# a.net
KiCad netlist of a schematic drawn in EAGLE
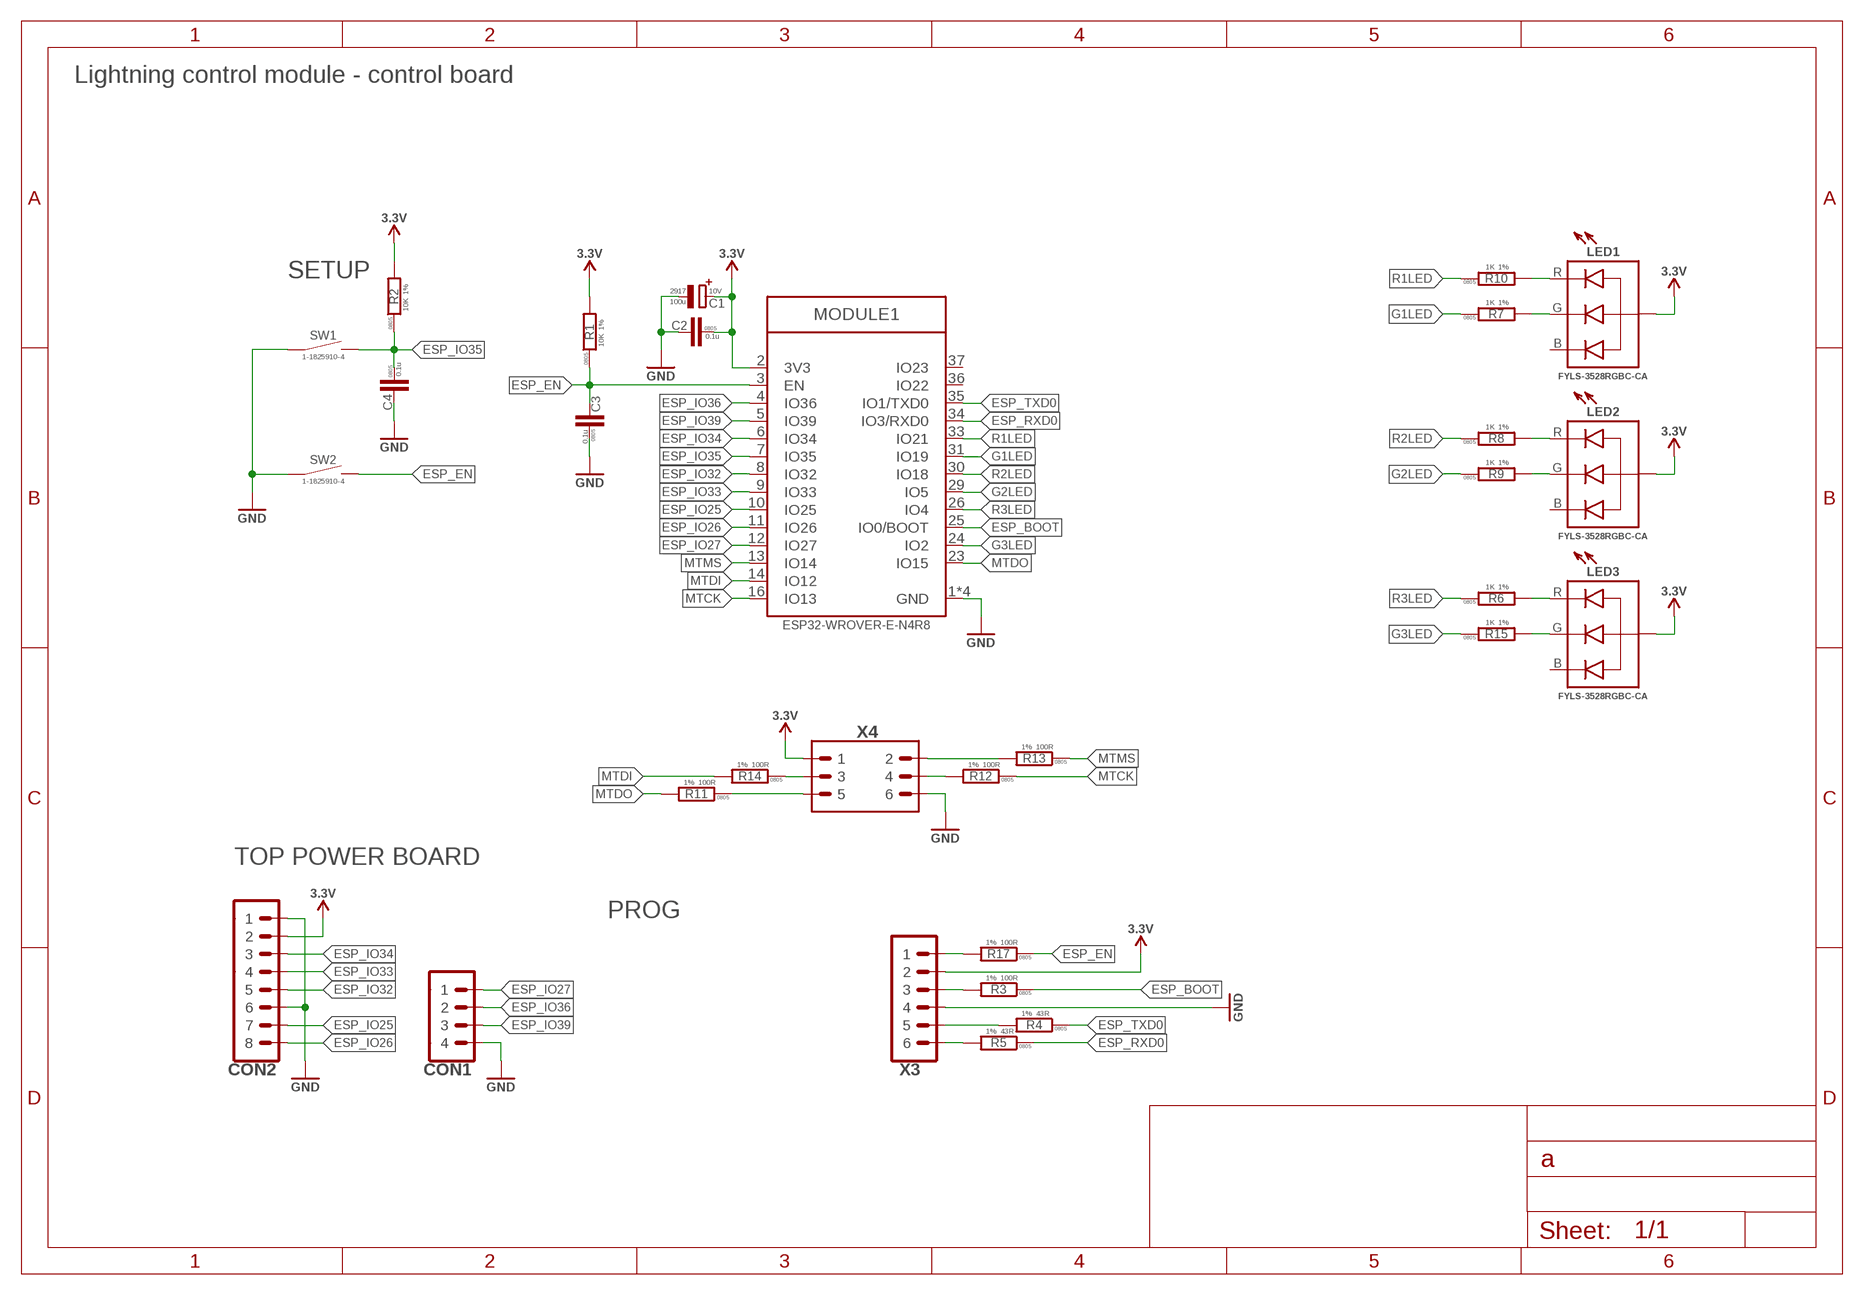
[diagram p0: schematic, sheet 1]

(export (version "E")
  (design (tool "Eeschema 10.0.6"))
  (components
    (comp (ref "C1")
      (value "100u")
      (footprint "eagle-import:C2917")
      (fields (field (name "PACKAGE") "2917") (field (name "VOLTAGE") "10V"))
      (libsource (lib "eagle-import") (part "CPOL-2917"))
    )
    (comp (ref "C2")
      (value "0.1u")
      (footprint "eagle-import:C0805")
      (fields (field (name "PACKAGE") "0805"))
      (libsource (lib "eagle-import") (part "C-0805"))
    )
    (comp (ref "C3")
      (value "0.1u")
      (footprint "eagle-import:C0805")
      (fields (field (name "PACKAGE") "0805"))
      (libsource (lib "eagle-import") (part "C-0805"))
    )
    (comp (ref "C4")
      (value "0.1u")
      (footprint "eagle-import:C0805")
      (fields (field (name "PACKAGE") "0805"))
      (libsource (lib "eagle-import") (part "C-0805"))
    )
    (comp (ref "CON1")
      (value "PINHEAD_1X04-2.54")
      (footprint "eagle-import:1X04-PTH-2.54")
      (libsource (lib "eagle-import") (part "PINHEAD_1X04-2.54"))
    )
    (comp (ref "CON2")
      (value "PINHEAD_1X08-2.54")
      (footprint "eagle-import:1X08-PTH-2.54")
      (libsource (lib "eagle-import") (part "PINHEAD_1X08-2.54"))
    )
    (comp (ref "LED1")
      (value "LED_RGB-3528")
      (footprint "eagle-import:LED3528")
      (fields (field (name "MANF#") "FYLS-3528RGBC-CA") (field (name "MANF") "Foryard"))
      (libsource (lib "eagle-import") (part "LED_RGB-3528"))
    )
    (comp (ref "LED2")
      (value "LED_RGB-3528")
      (footprint "eagle-import:LED3528")
      (fields (field (name "MANF#") "FYLS-3528RGBC-CA") (field (name "MANF") "Foryard"))
      (libsource (lib "eagle-import") (part "LED_RGB-3528"))
    )
    (comp (ref "LED3")
      (value "LED_RGB-3528")
      (footprint "eagle-import:LED3528")
      (fields (field (name "MANF#") "FYLS-3528RGBC-CA") (field (name "MANF") "Foryard"))
      (libsource (lib "eagle-import") (part "LED_RGB-3528"))
    )
    (comp (ref "MODULE1")
      (value "ESP32-WROVER-(I)E")
      (footprint "eagle-import:ESP32-WROVER-E")
      (fields (field (name "MANF#") "ESP32-WROVER-E-N4R8") (field (name "MANF") "Espressif Systems"))
      (libsource (lib "eagle-import") (part "ESP32-WROVER-(I)E"))
    )
    (comp (ref "R1")
      (value "10K")
      (footprint "eagle-import:R0805")
      (fields (field (name "PACKAGE") "0805") (field (name "TOLERANCE") "1%"))
      (libsource (lib "eagle-import") (part "R-0805-1%"))
    )
    (comp (ref "R2")
      (value "10K")
      (footprint "eagle-import:R0805")
      (fields (field (name "PACKAGE") "0805") (field (name "TOLERANCE") "1%"))
      (libsource (lib "eagle-import") (part "R-0805-1%"))
    )
    (comp (ref "R3")
      (value "100R")
      (footprint "eagle-import:R0805")
      (fields (field (name "PACKAGE") "0805") (field (name "TOLERANCE") "1%"))
      (libsource (lib "eagle-import") (part "R-0805-1%"))
    )
    (comp (ref "R4")
      (value "43R")
      (footprint "eagle-import:R0805")
      (fields (field (name "PACKAGE") "0805") (field (name "TOLERANCE") "1%"))
      (libsource (lib "eagle-import") (part "R-0805-1%"))
    )
    (comp (ref "R5")
      (value "43R")
      (footprint "eagle-import:R0805")
      (fields (field (name "PACKAGE") "0805") (field (name "TOLERANCE") "1%"))
      (libsource (lib "eagle-import") (part "R-0805-1%"))
    )
    (comp (ref "R6")
      (value "1K")
      (footprint "eagle-import:R0805")
      (fields (field (name "PACKAGE") "0805") (field (name "TOLERANCE") "1%"))
      (libsource (lib "eagle-import") (part "R-0805-1%"))
    )
    (comp (ref "R7")
      (value "1K")
      (footprint "eagle-import:R0805")
      (fields (field (name "PACKAGE") "0805") (field (name "TOLERANCE") "1%"))
      (libsource (lib "eagle-import") (part "R-0805-1%"))
    )
    (comp (ref "R8")
      (value "1K")
      (footprint "eagle-import:R0805")
      (fields (field (name "PACKAGE") "0805") (field (name "TOLERANCE") "1%"))
      (libsource (lib "eagle-import") (part "R-0805-1%"))
    )
    (comp (ref "R9")
      (value "1K")
      (footprint "eagle-import:R0805")
      (fields (field (name "PACKAGE") "0805") (field (name "TOLERANCE") "1%"))
      (libsource (lib "eagle-import") (part "R-0805-1%"))
    )
    (comp (ref "R10")
      (value "1K")
      (footprint "eagle-import:R0805")
      (fields (field (name "PACKAGE") "0805") (field (name "TOLERANCE") "1%"))
      (libsource (lib "eagle-import") (part "R-0805-1%"))
    )
    (comp (ref "R11")
      (value "100R")
      (footprint "eagle-import:R0805")
      (fields (field (name "PACKAGE") "0805") (field (name "TOLERANCE") "1%"))
      (libsource (lib "eagle-import") (part "R-0805-1%"))
    )
    (comp (ref "R12")
      (value "100R")
      (footprint "eagle-import:R0805")
      (fields (field (name "PACKAGE") "0805") (field (name "TOLERANCE") "1%"))
      (libsource (lib "eagle-import") (part "R-0805-1%"))
    )
    (comp (ref "R13")
      (value "100R")
      (footprint "eagle-import:R0805")
      (fields (field (name "PACKAGE") "0805") (field (name "TOLERANCE") "1%"))
      (libsource (lib "eagle-import") (part "R-0805-1%"))
    )
    (comp (ref "R14")
      (value "100R")
      (footprint "eagle-import:R0805")
      (fields (field (name "PACKAGE") "0805") (field (name "TOLERANCE") "1%"))
      (libsource (lib "eagle-import") (part "R-0805-1%"))
    )
    (comp (ref "R15")
      (value "1K")
      (footprint "eagle-import:R0805")
      (fields (field (name "PACKAGE") "0805") (field (name "TOLERANCE") "1%"))
      (libsource (lib "eagle-import") (part "R-0805-1%"))
    )
    (comp (ref "R17")
      (value "100R")
      (footprint "eagle-import:R0805")
      (fields (field (name "PACKAGE") "0805") (field (name "TOLERANCE") "1%"))
      (libsource (lib "eagle-import") (part "R-0805-1%"))
    )
    (comp (ref "SW1")
      (value "TACT_SWITCH-1-1825910-4")
      (footprint "eagle-import:1-1825910-4")
      (fields (field (name "MANF") "TE Connectivity"))
      (libsource (lib "eagle-import") (part "TACT_SWITCH-1-1825910-4"))
    )
    (comp (ref "SW2")
      (value "TACT_SWITCH-1-1825910-4")
      (footprint "eagle-import:1-1825910-4")
      (fields (field (name "MANF") "TE Connectivity"))
      (libsource (lib "eagle-import") (part "TACT_SWITCH-1-1825910-4"))
    )
    (comp (ref "X3")
      (value "PINHEAD_1X06-2-MALE")
      (footprint "eagle-import:1X06-PTH-2")
      (libsource (lib "eagle-import") (part "PINHEAD_1X06-2-MALE"))
    )
    (comp (ref "X4")
      (value "PINHEAD_2X03-PTH-2.54")
      (footprint "eagle-import:2X03-PTH-2.54")
      (libsource (lib "eagle-import") (part "PINHEAD_2X03-PTH-2.54"))
    )
  )
  (nets
    (net (code "1") (name "3.3V") (class "Default")
      (node (ref "C1") (pin "+") (pinfunction "+_+") (pintype "passive"))
      (node (ref "C2") (pin "1") (pinfunction "1_1") (pintype "passive"))
      (node (ref "CON2") (pin "2") (pinfunction "2_2") (pintype "passive"))
      (node (ref "LED1") (pin "2") (pinfunction "A_2") (pintype "bidirectional"))
      (node (ref "LED2") (pin "2") (pinfunction "A_2") (pintype "bidirectional"))
      (node (ref "LED3") (pin "2") (pinfunction "A_2") (pintype "bidirectional"))
      (node (ref "MODULE1") (pin "2") (pinfunction "3V3_2") (pintype "passive"))
      (node (ref "R1") (pin "2") (pinfunction "2_2") (pintype "passive"))
      (node (ref "R2") (pin "2") (pinfunction "2_2") (pintype "passive"))
      (node (ref "X3") (pin "2") (pinfunction "2_2") (pintype "passive"))
      (node (ref "X4") (pin "1") (pinfunction "1_1") (pintype "passive"))
    )
    (net (code "2") (name "ESP_BOOT") (class "Default")
      (node (ref "MODULE1") (pin "25") (pinfunction "IO0/BOOT_25") (pintype "tri_state"))
      (node (ref "R3") (pin "1") (pinfunction "1_1") (pintype "passive"))
    )
    (net (code "3") (name "ESP_EN") (class "Default")
      (node (ref "C3") (pin "2") (pinfunction "2_2") (pintype "passive"))
      (node (ref "MODULE1") (pin "3") (pinfunction "EN_3") (pintype "tri_state"))
      (node (ref "R1") (pin "1") (pinfunction "1_1") (pintype "passive"))
      (node (ref "R17") (pin "1") (pinfunction "1_1") (pintype "passive"))
      (node (ref "SW2") (pin "3") (pinfunction "2_3") (pintype "bidirectional"))
      (node (ref "SW2") (pin "4") (pinfunction "2_4") (pintype "bidirectional"))
    )
    (net (code "4") (name "ESP_IO25") (class "Default")
      (node (ref "CON2") (pin "7") (pinfunction "7_7") (pintype "passive"))
      (node (ref "MODULE1") (pin "10") (pinfunction "IO25_10") (pintype "tri_state"))
    )
    (net (code "5") (name "ESP_IO26") (class "Default")
      (node (ref "CON2") (pin "8") (pinfunction "8_8") (pintype "passive"))
      (node (ref "MODULE1") (pin "11") (pinfunction "IO26_11") (pintype "tri_state"))
    )
    (net (code "6") (name "ESP_IO27") (class "Default")
      (node (ref "CON1") (pin "1") (pinfunction "1_1") (pintype "passive"))
      (node (ref "MODULE1") (pin "12") (pinfunction "IO27_12") (pintype "tri_state"))
    )
    (net (code "7") (name "ESP_IO32") (class "Default")
      (node (ref "CON2") (pin "5") (pinfunction "5_5") (pintype "passive"))
      (node (ref "MODULE1") (pin "8") (pinfunction "IO32_8") (pintype "tri_state"))
    )
    (net (code "8") (name "ESP_IO33") (class "Default")
      (node (ref "CON2") (pin "4") (pinfunction "4_4") (pintype "passive"))
      (node (ref "MODULE1") (pin "9") (pinfunction "IO33_9") (pintype "tri_state"))
    )
    (net (code "9") (name "ESP_IO34") (class "Default")
      (node (ref "CON2") (pin "3") (pinfunction "3_3") (pintype "passive"))
      (node (ref "MODULE1") (pin "6") (pinfunction "IO34_6") (pintype "tri_state"))
    )
    (net (code "10") (name "ESP_IO35") (class "Default")
      (node (ref "C4") (pin "1") (pinfunction "1_1") (pintype "passive"))
      (node (ref "MODULE1") (pin "7") (pinfunction "IO35_7") (pintype "tri_state"))
      (node (ref "R2") (pin "1") (pinfunction "1_1") (pintype "passive"))
      (node (ref "SW1") (pin "3") (pinfunction "2_3") (pintype "bidirectional"))
      (node (ref "SW1") (pin "4") (pinfunction "2_4") (pintype "bidirectional"))
    )
    (net (code "11") (name "ESP_IO36") (class "Default")
      (node (ref "CON1") (pin "2") (pinfunction "2_2") (pintype "passive"))
      (node (ref "MODULE1") (pin "4") (pinfunction "IO36_4") (pintype "tri_state"))
    )
    (net (code "12") (name "ESP_IO39") (class "Default")
      (node (ref "CON1") (pin "3") (pinfunction "3_3") (pintype "passive"))
      (node (ref "MODULE1") (pin "5") (pinfunction "IO39_5") (pintype "tri_state"))
    )
    (net (code "13") (name "ESP_RXD0") (class "Default")
      (node (ref "MODULE1") (pin "34") (pinfunction "IO3/RXD0_34") (pintype "tri_state"))
      (node (ref "R5") (pin "1") (pinfunction "1_1") (pintype "passive"))
    )
    (net (code "14") (name "ESP_TXD0") (class "Default")
      (node (ref "MODULE1") (pin "35") (pinfunction "IO1/TXD0_35") (pintype "tri_state"))
      (node (ref "R4") (pin "1") (pinfunction "1_1") (pintype "passive"))
    )
    (net (code "15") (name "G1LED") (class "Default")
      (node (ref "MODULE1") (pin "31") (pinfunction "IO19_31") (pintype "tri_state"))
      (node (ref "R7") (pin "1") (pinfunction "1_1") (pintype "passive"))
    )
    (net (code "16") (name "G2LED") (class "Default")
      (node (ref "MODULE1") (pin "29") (pinfunction "IO5_29") (pintype "tri_state"))
      (node (ref "R9") (pin "1") (pinfunction "1_1") (pintype "passive"))
    )
    (net (code "17") (name "G3LED") (class "Default")
      (node (ref "MODULE1") (pin "24") (pinfunction "IO2_24") (pintype "tri_state"))
      (node (ref "R15") (pin "1") (pinfunction "1_1") (pintype "passive"))
    )
    (net (code "18") (name "GND") (class "Default")
      (node (ref "C1") (pin "-") (pinfunction "-_-") (pintype "passive"))
      (node (ref "C2") (pin "2") (pinfunction "2_2") (pintype "passive"))
      (node (ref "C3") (pin "1") (pinfunction "1_1") (pintype "passive"))
      (node (ref "C4") (pin "2") (pinfunction "2_2") (pintype "passive"))
      (node (ref "CON1") (pin "4") (pinfunction "4_4") (pintype "passive"))
      (node (ref "CON2") (pin "1") (pinfunction "1_1") (pintype "passive"))
      (node (ref "CON2") (pin "6") (pinfunction "6_6") (pintype "passive"))
      (node (ref "MODULE1") (pin "1") (pinfunction "GND_1") (pintype "tri_state"))
      (node (ref "MODULE1") (pin "15") (pinfunction "GND_15") (pintype "tri_state"))
      (node (ref "MODULE1") (pin "38") (pinfunction "GND_38") (pintype "tri_state"))
      (node (ref "MODULE1") (pin "39") (pinfunction "GND_39") (pintype "tri_state"))
      (node (ref "SW1") (pin "1") (pinfunction "1_1") (pintype "bidirectional"))
      (node (ref "SW1") (pin "2") (pinfunction "1_2") (pintype "bidirectional"))
      (node (ref "SW2") (pin "1") (pinfunction "1_1") (pintype "bidirectional"))
      (node (ref "SW2") (pin "2") (pinfunction "1_2") (pintype "bidirectional"))
      (node (ref "X3") (pin "4") (pinfunction "4_4") (pintype "passive"))
      (node (ref "X4") (pin "6") (pinfunction "6_6") (pintype "passive"))
    )
    (net (code "19") (name "MTCK") (class "Default")
      (node (ref "MODULE1") (pin "16") (pinfunction "IO13_16") (pintype "tri_state"))
      (node (ref "R12") (pin "1") (pinfunction "1_1") (pintype "passive"))
    )
    (net (code "20") (name "MTDI") (class "Default")
      (node (ref "MODULE1") (pin "14") (pinfunction "IO12_14") (pintype "tri_state"))
      (node (ref "R14") (pin "2") (pinfunction "2_2") (pintype "passive"))
    )
    (net (code "21") (name "MTDO") (class "Default")
      (node (ref "MODULE1") (pin "23") (pinfunction "IO15_23") (pintype "tri_state"))
      (node (ref "R11") (pin "2") (pinfunction "2_2") (pintype "passive"))
    )
    (net (code "22") (name "MTMS") (class "Default")
      (node (ref "MODULE1") (pin "13") (pinfunction "IO14_13") (pintype "tri_state"))
      (node (ref "R13") (pin "1") (pinfunction "1_1") (pintype "passive"))
    )
    (net (code "23") (name "Net-(LED1-G)") (class "Default")
      (node (ref "LED1") (pin "4") (pinfunction "G_4") (pintype "bidirectional"))
      (node (ref "R7") (pin "2") (pinfunction "2_2") (pintype "passive"))
    )
    (net (code "24") (name "Net-(LED1-R)") (class "Default")
      (node (ref "LED1") (pin "1") (pinfunction "R_1") (pintype "bidirectional"))
      (node (ref "R10") (pin "2") (pinfunction "2_2") (pintype "passive"))
    )
    (net (code "25") (name "Net-(LED2-G)") (class "Default")
      (node (ref "LED2") (pin "4") (pinfunction "G_4") (pintype "bidirectional"))
      (node (ref "R9") (pin "2") (pinfunction "2_2") (pintype "passive"))
    )
    (net (code "26") (name "Net-(LED2-R)") (class "Default")
      (node (ref "LED2") (pin "1") (pinfunction "R_1") (pintype "bidirectional"))
      (node (ref "R8") (pin "2") (pinfunction "2_2") (pintype "passive"))
    )
    (net (code "27") (name "Net-(LED3-G)") (class "Default")
      (node (ref "LED3") (pin "4") (pinfunction "G_4") (pintype "bidirectional"))
      (node (ref "R15") (pin "2") (pinfunction "2_2") (pintype "passive"))
    )
    (net (code "28") (name "Net-(LED3-R)") (class "Default")
      (node (ref "LED3") (pin "1") (pinfunction "R_1") (pintype "bidirectional"))
      (node (ref "R6") (pin "2") (pinfunction "2_2") (pintype "passive"))
    )
    (net (code "29") (name "Net-(R3-Pad2)") (class "Default")
      (node (ref "R3") (pin "2") (pinfunction "2_2") (pintype "passive"))
      (node (ref "X3") (pin "3") (pinfunction "3_3") (pintype "passive"))
    )
    (net (code "30") (name "Net-(R4-Pad2)") (class "Default")
      (node (ref "R4") (pin "2") (pinfunction "2_2") (pintype "passive"))
      (node (ref "X3") (pin "5") (pinfunction "5_5") (pintype "passive"))
    )
    (net (code "31") (name "Net-(R5-Pad2)") (class "Default")
      (node (ref "R5") (pin "2") (pinfunction "2_2") (pintype "passive"))
      (node (ref "X3") (pin "6") (pinfunction "6_6") (pintype "passive"))
    )
    (net (code "32") (name "Net-(R11-Pad1)") (class "Default")
      (node (ref "R11") (pin "1") (pinfunction "1_1") (pintype "passive"))
      (node (ref "X4") (pin "5") (pinfunction "5_5") (pintype "passive"))
    )
    (net (code "33") (name "Net-(R12-Pad2)") (class "Default")
      (node (ref "R12") (pin "2") (pinfunction "2_2") (pintype "passive"))
      (node (ref "X4") (pin "4") (pinfunction "4_4") (pintype "passive"))
    )
    (net (code "34") (name "Net-(R13-Pad2)") (class "Default")
      (node (ref "R13") (pin "2") (pinfunction "2_2") (pintype "passive"))
      (node (ref "X4") (pin "2") (pinfunction "2_2") (pintype "passive"))
    )
    (net (code "35") (name "Net-(R14-Pad1)") (class "Default")
      (node (ref "R14") (pin "1") (pinfunction "1_1") (pintype "passive"))
      (node (ref "X4") (pin "3") (pinfunction "3_3") (pintype "passive"))
    )
    (net (code "36") (name "Net-(R17-Pad2)") (class "Default")
      (node (ref "R17") (pin "2") (pinfunction "2_2") (pintype "passive"))
      (node (ref "X3") (pin "1") (pinfunction "1_1") (pintype "passive"))
    )
    (net (code "37") (name "R1LED") (class "Default")
      (node (ref "MODULE1") (pin "33") (pinfunction "IO21_33") (pintype "tri_state"))
      (node (ref "R10") (pin "1") (pinfunction "1_1") (pintype "passive"))
    )
    (net (code "38") (name "R2LED") (class "Default")
      (node (ref "MODULE1") (pin "30") (pinfunction "IO18_30") (pintype "tri_state"))
      (node (ref "R8") (pin "1") (pinfunction "1_1") (pintype "passive"))
    )
    (net (code "39") (name "R3LED") (class "Default")
      (node (ref "MODULE1") (pin "26") (pinfunction "IO4_26") (pintype "tri_state"))
      (node (ref "R6") (pin "1") (pinfunction "1_1") (pintype "passive"))
    )
    (net (code "40") (name "unconnected-(LED1-B-Pad3)") (class "Default")
      (node (ref "LED1") (pin "3") (pinfunction "B_3") (pintype "bidirectional"))
    )
    (net (code "41") (name "unconnected-(LED2-B-Pad3)") (class "Default")
      (node (ref "LED2") (pin "3") (pinfunction "B_3") (pintype "bidirectional"))
    )
    (net (code "42") (name "unconnected-(LED3-B-Pad3)") (class "Default")
      (node (ref "LED3") (pin "3") (pinfunction "B_3") (pintype "bidirectional"))
    )
    (net (code "43") (name "unconnected-(MODULE1-IO22-Pad36)") (class "Default")
      (node (ref "MODULE1") (pin "36") (pinfunction "IO22_36") (pintype "tri_state"))
    )
    (net (code "44") (name "unconnected-(MODULE1-IO23-Pad37)") (class "Default")
      (node (ref "MODULE1") (pin "37") (pinfunction "IO23_37") (pintype "tri_state"))
    )
  )
)
